# power2V5.net
KiCad netlist of a schematic drawn in Altium Designer
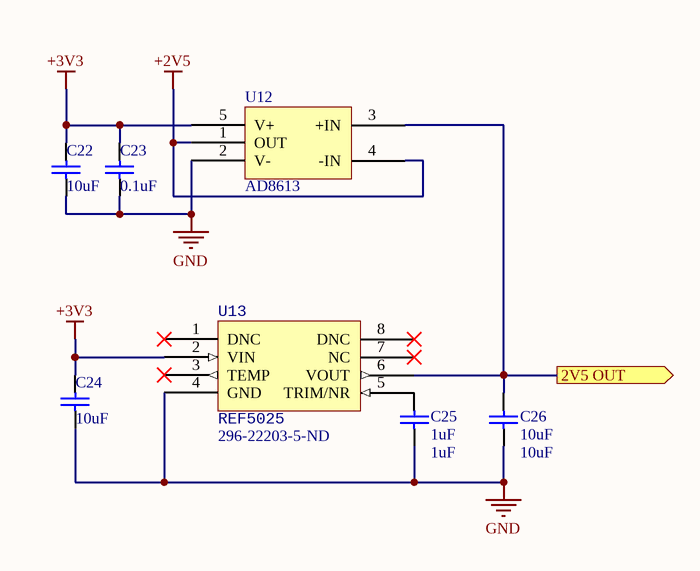
[diagram p0: power2V5.SchDoc]

(export (version "E")
  (design (tool "Eeschema 10.0.6"))
  (components
    (comp (ref "C22")
      (value "10uF")
      (footprint "1608[0603]")
      (description "Capacitor (Semiconductor SIM Model)")
      (fields (field (name "PUBLISHER") "Altium Limited"))
      (libsource (lib "Miscellaneous Devices") (part "Cap Semi"))
    )
    (comp (ref "C23")
      (value "0.1uF")
      (footprint "1608[0603]")
      (description "Capacitor (Semiconductor SIM Model)")
      (fields (field (name "PUBLISHER") "Altium Limited"))
      (libsource (lib "Miscellaneous Devices") (part "Cap Semi"))
    )
    (comp (ref "C24")
      (value "10uF")
      (footprint "1608[0603]")
      (description "Capacitor (Semiconductor SIM Model)")
      (fields (field (name "PUBLISHER") "Altium Limited"))
      (libsource (lib "Miscellaneous Devices") (part "Cap Semi"))
    )
    (comp (ref "C25")
      (value "1uF")
      (footprint "1608[0603]")
      (description "Capacitor (Semiconductor SIM Model)")
      (fields (field (name "ALTIUM_VALUE") "1uF") (field (name "PUBLISHER") "Altium Limited"))
      (libsource (lib "Miscellaneous Devices") (part "Cap Semi"))
    )
    (comp (ref "C26")
      (value "10uF")
      (footprint "1608[0603]")
      (description "Capacitor (Semiconductor SIM Model)")
      (fields (field (name "ALTIUM_VALUE") "10uF") (field (name "PUBLISHER") "Altium Limited"))
      (libsource (lib "Miscellaneous Devices") (part "Cap Semi"))
    )
    (comp (ref "U12")
      (value "AD8613")
      (footprint "SOP-65P200X125-5N")
      (description "Low power, low noise rail-to-rail op-amp.")
      (libsource (lib "PAY") (part "AD8613"))
    )
    (comp (ref "U13")
      (value "REF5025")
      (footprint "SOIC127P500X600-8N")
      (description "Voltage Reference")
      (fields (field (name "SUPPLIER PART NUMBER 1") "296-22203-5-ND"))
      (libsource (lib "heron-general") (part "REF5025"))
    )
  )
  (nets
    (net (code "1") (name "+2V5") (class "Default")
      (node (ref "U12") (pin "1") (pinfunction "OUT_1") (pintype "passive"))
      (node (ref "U12") (pin "4") (pinfunction "-IN_4") (pintype "passive"))
    )
    (net (code "2") (name "+3V3") (class "Default")
      (node (ref "C22") (pin "2") (pinfunction "2_2") (pintype "passive"))
      (node (ref "C23") (pin "2") (pinfunction "2_2") (pintype "passive"))
      (node (ref "C24") (pin "2") (pinfunction "2_2") (pintype "passive"))
      (node (ref "U12") (pin "5") (pinfunction "V+_5") (pintype "passive"))
      (node (ref "U13") (pin "2") (pinfunction "VIN_2") (pintype "input"))
    )
    (net (code "3") (name "/2V5 OUT") (class "Default")
      (node (ref "C26") (pin "2") (pinfunction "2_2") (pintype "passive"))
      (node (ref "U12") (pin "3") (pinfunction "+IN_3") (pintype "passive"))
      (node (ref "U13") (pin "6") (pinfunction "VOUT_6") (pintype "output"))
    )
    (net (code "4") (name "GND") (class "Default")
      (node (ref "C22") (pin "1") (pinfunction "1_1") (pintype "passive"))
      (node (ref "C23") (pin "1") (pinfunction "1_1") (pintype "passive"))
      (node (ref "C24") (pin "1") (pinfunction "1_1") (pintype "passive"))
      (node (ref "C25") (pin "1") (pinfunction "1_1") (pintype "passive"))
      (node (ref "C26") (pin "1") (pinfunction "1_1") (pintype "passive"))
      (node (ref "U12") (pin "2") (pinfunction "V-_2") (pintype "passive"))
      (node (ref "U13") (pin "4") (pinfunction "GND_4") (pintype "power_in"))
    )
    (net (code "5") (name "Net-(U13-TRIM{slash}NR)") (class "Default")
      (node (ref "C25") (pin "2") (pinfunction "2_2") (pintype "passive"))
      (node (ref "U13") (pin "5") (pinfunction "TRIM/NR_5") (pintype "input"))
    )
    (net (code "6") (name "unconnected-(U13-DNC-Pad1)") (class "Default")
      (node (ref "U13") (pin "1") (pinfunction "DNC_1") (pintype "passive+no_connect"))
    )
    (net (code "7") (name "unconnected-(U13-DNC-Pad8)") (class "Default")
      (node (ref "U13") (pin "8") (pinfunction "DNC_8") (pintype "passive+no_connect"))
    )
    (net (code "8") (name "unconnected-(U13-NC-Pad7)") (class "Default")
      (node (ref "U13") (pin "7") (pinfunction "NC_7") (pintype "passive+no_connect"))
    )
    (net (code "9") (name "unconnected-(U13-TEMP-Pad3)") (class "Default")
      (node (ref "U13") (pin "3") (pinfunction "TEMP_3") (pintype "output+no_connect"))
    )
  )
)
